# transistor_op-amp_v2_SIP.net
KiCad netlist of a schematic drawn in EAGLE
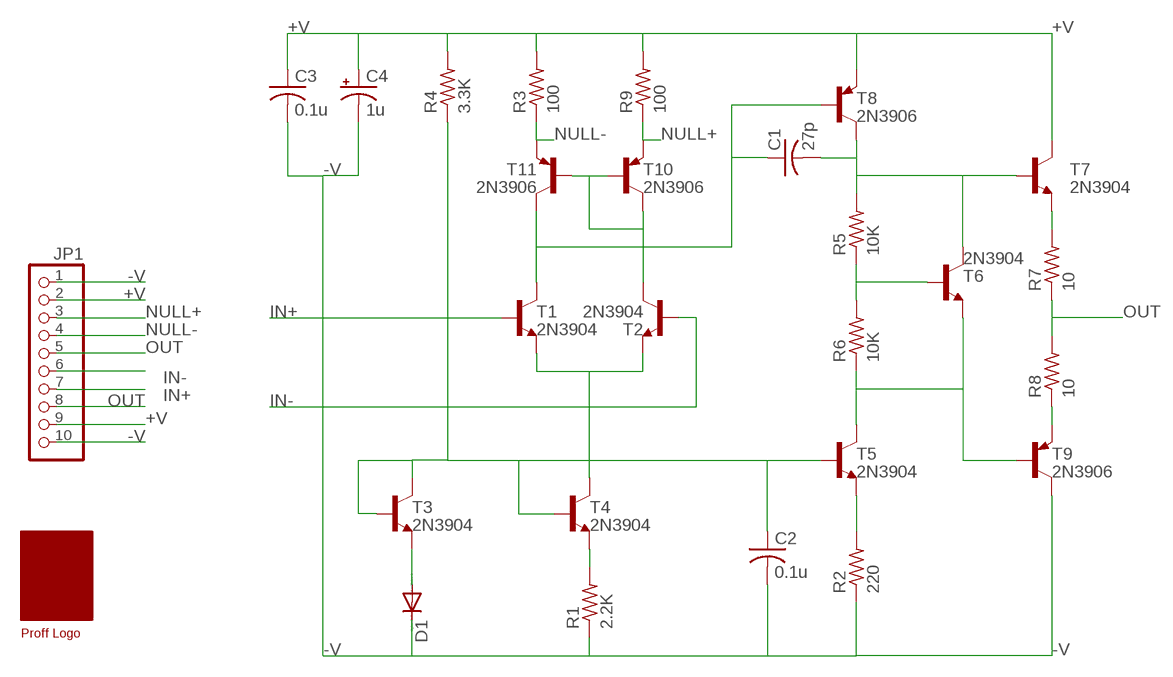
[diagram p0: schematic, sheet 1]

(export (version "E")
  (design (tool "Eeschema 10.0.6"))
  (components
    (comp (ref "C1")
      (value "27p")
      (footprint "eagle-import:C050-024X044")
      (libsource (lib "eagle-import") (part "C-US050-024X044"))
    )
    (comp (ref "C2")
      (value "0.1u")
      (footprint "eagle-import:C050-024X044")
      (libsource (lib "eagle-import") (part "C-US050-024X044"))
    )
    (comp (ref "C3")
      (value "0.1u")
      (footprint "eagle-import:C050-024X044")
      (libsource (lib "eagle-import") (part "C-US050-024X044"))
    )
    (comp (ref "C4")
      (value "1u")
      (footprint "eagle-import:E2,5-5")
      (libsource (lib "eagle-import") (part "CPOL-USE2.5-5"))
    )
    (comp (ref "D1")
      (value "DIODE-D-7.5")
      (footprint "eagle-import:D-7.5")
      (libsource (lib "eagle-import") (part "DIODE-D-7.5"))
    )
    (comp (ref "JP1")
      (value "PINHD-1X10")
      (footprint "eagle-import:1X10")
      (libsource (lib "eagle-import") (part "PINHD-1X10"))
    )
    (comp (ref "R1")
      (value "2.2K")
      (footprint "eagle-import:0207_7")
      (libsource (lib "eagle-import") (part "R-US_0207/7"))
    )
    (comp (ref "R2")
      (value "220")
      (footprint "eagle-import:0207_7")
      (libsource (lib "eagle-import") (part "R-US_0207/7"))
    )
    (comp (ref "R3")
      (value "100")
      (footprint "eagle-import:0207_7")
      (libsource (lib "eagle-import") (part "R-US_0207/7"))
    )
    (comp (ref "R4")
      (value "3.3K")
      (footprint "eagle-import:0207_7")
      (libsource (lib "eagle-import") (part "R-US_0207/7"))
    )
    (comp (ref "R5")
      (value "10K")
      (footprint "eagle-import:0207_7")
      (libsource (lib "eagle-import") (part "R-US_0207/7"))
    )
    (comp (ref "R6")
      (value "10K")
      (footprint "eagle-import:0207_7")
      (libsource (lib "eagle-import") (part "R-US_0207/7"))
    )
    (comp (ref "R7")
      (value "10")
      (footprint "eagle-import:0207_7")
      (libsource (lib "eagle-import") (part "R-US_0207/7"))
    )
    (comp (ref "R8")
      (value "10")
      (footprint "eagle-import:0207_7")
      (libsource (lib "eagle-import") (part "R-US_0207/7"))
    )
    (comp (ref "R9")
      (value "100")
      (footprint "eagle-import:0207_7")
      (libsource (lib "eagle-import") (part "R-US_0207/7"))
    )
    (comp (ref "T1")
      (value "2N3904")
      (footprint "eagle-import:TO92")
      (libsource (lib "eagle-import") (part "2N3904"))
    )
    (comp (ref "T2")
      (value "2N3904")
      (footprint "eagle-import:TO92")
      (libsource (lib "eagle-import") (part "2N3904"))
    )
    (comp (ref "T3")
      (value "2N3904")
      (footprint "eagle-import:TO92")
      (libsource (lib "eagle-import") (part "2N3904"))
    )
    (comp (ref "T4")
      (value "2N3904")
      (footprint "eagle-import:TO92")
      (libsource (lib "eagle-import") (part "2N3904"))
    )
    (comp (ref "T5")
      (value "2N3904")
      (footprint "eagle-import:TO92")
      (libsource (lib "eagle-import") (part "2N3904"))
    )
    (comp (ref "T6")
      (value "2N3904")
      (footprint "eagle-import:TO92")
      (libsource (lib "eagle-import") (part "2N3904"))
    )
    (comp (ref "T7")
      (value "2N3904")
      (footprint "eagle-import:TO92")
      (libsource (lib "eagle-import") (part "transistor-npn_2N3904"))
    )
    (comp (ref "T8")
      (value "2N3906")
      (footprint "eagle-import:TO92")
      (libsource (lib "eagle-import") (part "2N3906"))
    )
    (comp (ref "T9")
      (value "2N3906")
      (footprint "eagle-import:TO92")
      (libsource (lib "eagle-import") (part "2N3906"))
    )
    (comp (ref "T10")
      (value "2N3906")
      (footprint "eagle-import:TO92")
      (libsource (lib "eagle-import") (part "2N3906"))
    )
    (comp (ref "T11")
      (value "2N3906")
      (footprint "eagle-import:TO92")
      (libsource (lib "eagle-import") (part "2N3906"))
    )
    (comp (ref "U$1")
      (value "PROFF")
      (footprint "eagle-import:PROFF")
      (libsource (lib "eagle-import") (part "PROFF"))
    )
  )
  (nets
    (net (code "1") (name "/+V") (class "Default")
      (node (ref "C3") (pin "1") (pinfunction "1_1") (pintype "passive"))
      (node (ref "C4") (pin "+") (pinfunction "+_+") (pintype "passive"))
      (node (ref "JP1") (pin "2") (pinfunction "2_2") (pintype "passive"))
      (node (ref "JP1") (pin "9") (pinfunction "9_9") (pintype "passive"))
      (node (ref "R3") (pin "2") (pinfunction "2_2") (pintype "passive"))
      (node (ref "R4") (pin "2") (pinfunction "2_2") (pintype "passive"))
      (node (ref "R9") (pin "2") (pinfunction "2_2") (pintype "passive"))
      (node (ref "T7") (pin "1") (pinfunction "C_1") (pintype "passive"))
      (node (ref "T8") (pin "3") (pinfunction "E_3") (pintype "passive"))
    )
    (net (code "2") (name "/-V") (class "Default")
      (node (ref "C2") (pin "2") (pinfunction "2_2") (pintype "passive"))
      (node (ref "C3") (pin "2") (pinfunction "2_2") (pintype "passive"))
      (node (ref "C4") (pin "-") (pinfunction "-_-") (pintype "passive"))
      (node (ref "D1") (pin "C") (pinfunction "C_C") (pintype "passive"))
      (node (ref "JP1") (pin "1") (pinfunction "1_1") (pintype "passive"))
      (node (ref "JP1") (pin "10") (pinfunction "10_10") (pintype "passive"))
      (node (ref "R1") (pin "1") (pinfunction "1_1") (pintype "passive"))
      (node (ref "R2") (pin "1") (pinfunction "1_1") (pintype "passive"))
      (node (ref "T9") (pin "1") (pinfunction "C_1") (pintype "passive"))
    )
    (net (code "3") (name "/IN+") (class "Default")
      (node (ref "JP1") (pin "6") (pinfunction "6_6") (pintype "passive"))
      (node (ref "T1") (pin "2") (pinfunction "B_2") (pintype "passive"))
    )
    (net (code "4") (name "/IN-") (class "Default")
      (node (ref "JP1") (pin "7") (pinfunction "7_7") (pintype "passive"))
      (node (ref "T2") (pin "2") (pinfunction "B_2") (pintype "passive"))
    )
    (net (code "5") (name "/NULL+") (class "Default")
      (node (ref "JP1") (pin "3") (pinfunction "3_3") (pintype "passive"))
      (node (ref "R9") (pin "1") (pinfunction "1_1") (pintype "passive"))
      (node (ref "T10") (pin "3") (pinfunction "E_3") (pintype "passive"))
    )
    (net (code "6") (name "/NULL-") (class "Default")
      (node (ref "JP1") (pin "4") (pinfunction "4_4") (pintype "passive"))
      (node (ref "R3") (pin "1") (pinfunction "1_1") (pintype "passive"))
      (node (ref "T11") (pin "3") (pinfunction "E_3") (pintype "passive"))
    )
    (net (code "7") (name "/OUT") (class "Default")
      (node (ref "JP1") (pin "5") (pinfunction "5_5") (pintype "passive"))
      (node (ref "JP1") (pin "8") (pinfunction "8_8") (pintype "passive"))
      (node (ref "R7") (pin "1") (pinfunction "1_1") (pintype "passive"))
      (node (ref "R8") (pin "2") (pinfunction "2_2") (pintype "passive"))
    )
    (net (code "8") (name "Net-(T1-C)") (class "Default")
      (node (ref "C1") (pin "1") (pinfunction "1_1") (pintype "passive"))
      (node (ref "T1") (pin "1") (pinfunction "C_1") (pintype "passive"))
      (node (ref "T11") (pin "1") (pinfunction "C_1") (pintype "passive"))
      (node (ref "T8") (pin "2") (pinfunction "B_2") (pintype "passive"))
    )
    (net (code "9") (name "Net-(T1-E)") (class "Default")
      (node (ref "T1") (pin "3") (pinfunction "E_3") (pintype "passive"))
      (node (ref "T2") (pin "3") (pinfunction "E_3") (pintype "passive"))
      (node (ref "T4") (pin "1") (pinfunction "C_1") (pintype "passive"))
    )
    (net (code "10") (name "Net-(T3-B)") (class "Default")
      (node (ref "C2") (pin "1") (pinfunction "1_1") (pintype "passive"))
      (node (ref "R4") (pin "1") (pinfunction "1_1") (pintype "passive"))
      (node (ref "T3") (pin "1") (pinfunction "C_1") (pintype "passive"))
      (node (ref "T3") (pin "2") (pinfunction "B_2") (pintype "passive"))
      (node (ref "T4") (pin "2") (pinfunction "B_2") (pintype "passive"))
      (node (ref "T5") (pin "2") (pinfunction "B_2") (pintype "passive"))
    )
    (net (code "11") (name "Net-(T3-E)") (class "Default")
      (node (ref "D1") (pin "A") (pinfunction "A_A") (pintype "passive"))
      (node (ref "T3") (pin "3") (pinfunction "E_3") (pintype "passive"))
    )
    (net (code "12") (name "Net-(T4-E)") (class "Default")
      (node (ref "R1") (pin "2") (pinfunction "2_2") (pintype "passive"))
      (node (ref "T4") (pin "3") (pinfunction "E_3") (pintype "passive"))
    )
    (net (code "13") (name "Net-(T5-C)") (class "Default")
      (node (ref "R6") (pin "1") (pinfunction "1_1") (pintype "passive"))
      (node (ref "T5") (pin "1") (pinfunction "C_1") (pintype "passive"))
      (node (ref "T6") (pin "3") (pinfunction "E_3") (pintype "passive"))
      (node (ref "T9") (pin "2") (pinfunction "B_2") (pintype "passive"))
    )
    (net (code "14") (name "Net-(T5-E)") (class "Default")
      (node (ref "R2") (pin "2") (pinfunction "2_2") (pintype "passive"))
      (node (ref "T5") (pin "3") (pinfunction "E_3") (pintype "passive"))
    )
    (net (code "15") (name "Net-(T6-B)") (class "Default")
      (node (ref "R5") (pin "1") (pinfunction "1_1") (pintype "passive"))
      (node (ref "R6") (pin "2") (pinfunction "2_2") (pintype "passive"))
      (node (ref "T6") (pin "2") (pinfunction "B_2") (pintype "passive"))
    )
    (net (code "16") (name "Net-(T6-C)") (class "Default")
      (node (ref "C1") (pin "2") (pinfunction "2_2") (pintype "passive"))
      (node (ref "R5") (pin "2") (pinfunction "2_2") (pintype "passive"))
      (node (ref "T6") (pin "1") (pinfunction "C_1") (pintype "passive"))
      (node (ref "T7") (pin "2") (pinfunction "B_2") (pintype "passive"))
      (node (ref "T8") (pin "1") (pinfunction "C_1") (pintype "passive"))
    )
    (net (code "17") (name "Net-(T7-E)") (class "Default")
      (node (ref "R7") (pin "2") (pinfunction "2_2") (pintype "passive"))
      (node (ref "T7") (pin "3") (pinfunction "E_3") (pintype "passive"))
    )
    (net (code "18") (name "Net-(T9-E)") (class "Default")
      (node (ref "R8") (pin "1") (pinfunction "1_1") (pintype "passive"))
      (node (ref "T9") (pin "3") (pinfunction "E_3") (pintype "passive"))
    )
    (net (code "19") (name "Net-(T10-B)") (class "Default")
      (node (ref "T10") (pin "1") (pinfunction "C_1") (pintype "passive"))
      (node (ref "T10") (pin "2") (pinfunction "B_2") (pintype "passive"))
      (node (ref "T11") (pin "2") (pinfunction "B_2") (pintype "passive"))
      (node (ref "T2") (pin "1") (pinfunction "C_1") (pintype "passive"))
    )
  )
)
